# ESC2.net
KiCad netlist of a schematic drawn in Altium Designer
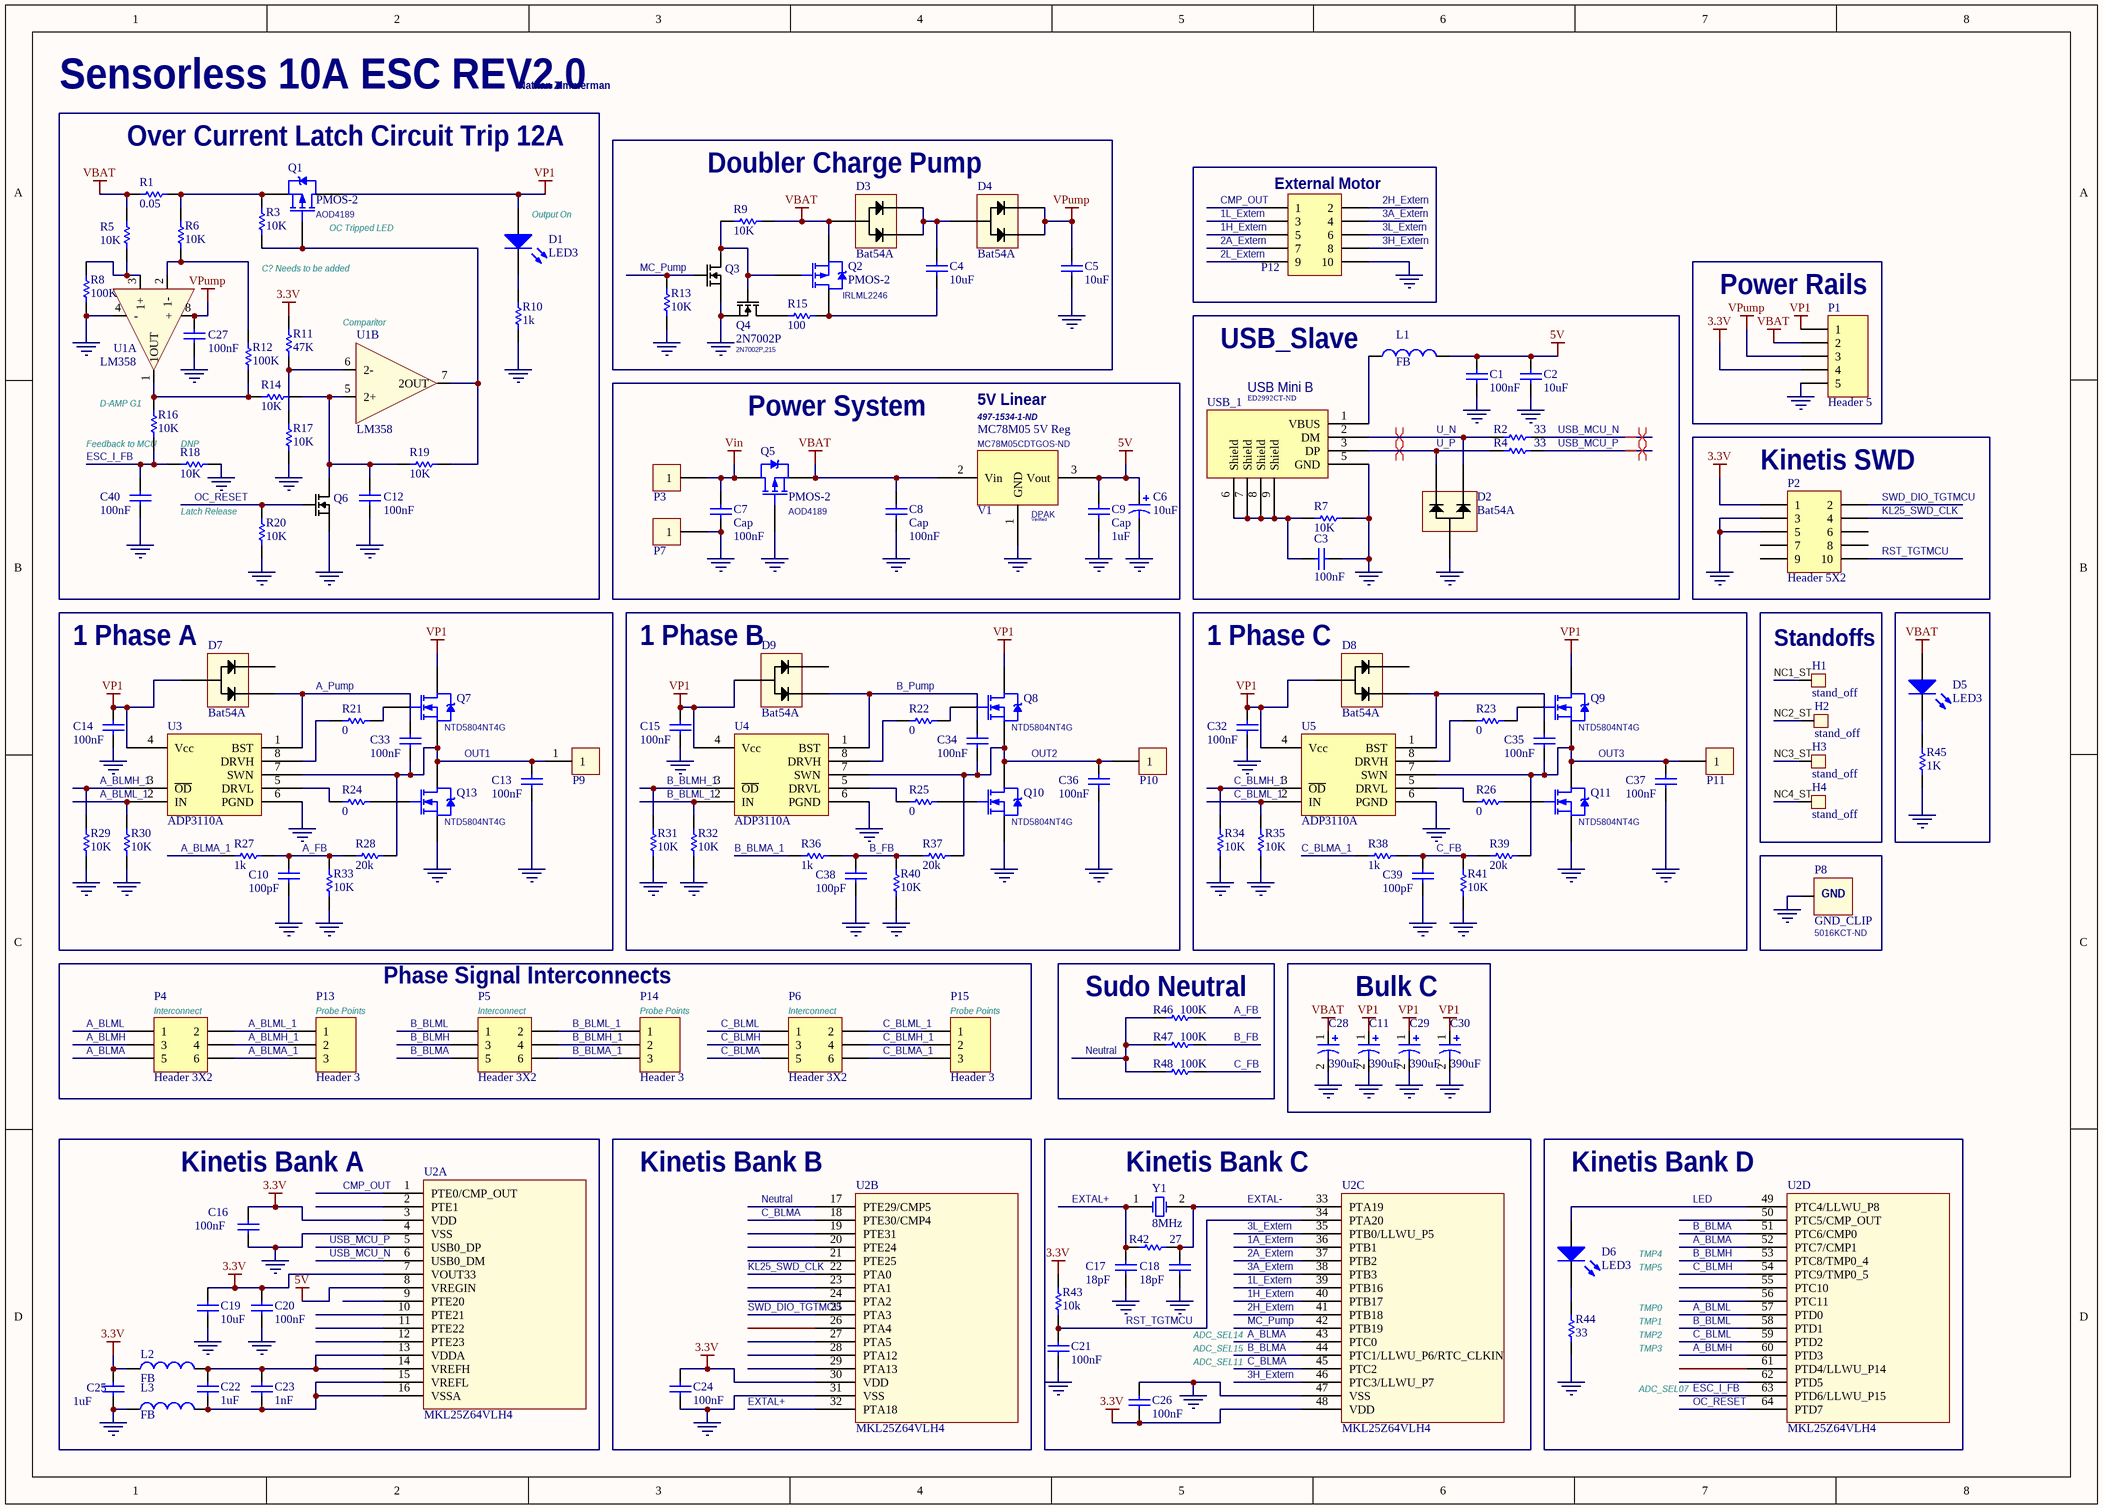
[diagram p0: ESC2.SchDoc]

(export (version "E")
  (design (tool "Eeschema 10.0.6"))
  (components
    (comp (ref "C1")
      (value "100nF")
      (footprint "1608[0603]")
      (description "Capacitor (Semiconductor SIM Model)")
      (fields (field (name "Comment") "0805") (field (name "PUBLISHER") "Altium Limited"))
      (libsource (lib "Miscellaneous Devices") (part "Cap Semi"))
    )
    (comp (ref "C2")
      (value "10uF")
      (footprint "C0805")
      (description "Capacitor (Semiconductor SIM Model)")
      (fields (field (name "Comment") "0805") (field (name "PUBLISHER") "Altium Limited"))
      (libsource (lib "Miscellaneous Devices") (part "Cap Semi"))
    )
    (comp (ref "C3")
      (value "100nF")
      (footprint "1608[0603]")
      (description "Capacitor (Semiconductor SIM Model)")
      (fields (field (name "Comment") "0805") (field (name "PUBLISHER") "Altium Limited"))
      (libsource (lib "Miscellaneous Devices") (part "Cap Semi"))
    )
    (comp (ref "C4")
      (value "10uF")
      (footprint "C0805")
      (description "Capacitor (Semiconductor SIM Model)")
      (fields (field (name "Comment") "0805") (field (name "PUBLISHER") "Altium Limited"))
      (libsource (lib "Miscellaneous Devices") (part "Cap Semi"))
    )
    (comp (ref "C5")
      (value "10uF")
      (footprint "C0805")
      (description "Capacitor (Semiconductor SIM Model)")
      (fields (field (name "Comment") "0805") (field (name "PUBLISHER") "Altium Limited"))
      (libsource (lib "Miscellaneous Devices") (part "Cap Semi"))
    )
    (comp (ref "C6")
      (value "10uF")
      (footprint "1206_C")
      (description "Polarized Capacitor (Radial)")
      (fields (field (name "Comment") "Cap Pol1"))
      (libsource (lib "") (part "Cap Pol1_1"))
    )
    (comp (ref "C7")
      (value "Cap")
      (footprint "C0805")
      (description "Capacitor")
      (fields (field (name "ALTIUM_VALUE") "100nF") (field (name "PUBLISHER") "Altium Limited"))
      (libsource (lib "Miscellaneous Devices") (part "Cap"))
    )
    (comp (ref "C8")
      (value "Cap")
      (footprint "C0805")
      (description "Capacitor")
      (fields (field (name "ALTIUM_VALUE") "100nF") (field (name "PUBLISHER") "Altium Limited"))
      (libsource (lib "Miscellaneous Devices") (part "Cap"))
    )
    (comp (ref "C9")
      (value "Cap")
      (footprint "C0805")
      (description "Capacitor")
      (fields (field (name "ALTIUM_VALUE") "1uF") (field (name "PUBLISHER") "Altium Limited"))
      (libsource (lib "Miscellaneous Devices") (part "Cap"))
    )
    (comp (ref "C10")
      (value "100pF")
      (footprint "1608[0603]")
      (description "Capacitor (Semiconductor SIM Model)")
      (fields (field (name "Comment") "0805") (field (name "PUBLISHER") "Altium Limited"))
      (libsource (lib "Miscellaneous Devices") (part "Cap Semi"))
    )
    (comp (ref "C11")
      (value "390uF")
      (footprint "EEE-FPV391UAP")
      (description "Polarized Capacitor (Radial)")
      (fields (field (name "PART #") "EEE-FPV391UAP") (field (name "Comment") "Cap Pol1"))
      (libsource (lib "Miscellaneous Devices") (part "Cap Pol1"))
    )
    (comp (ref "C12")
      (value "100nF")
      (footprint "1608[0603]")
      (description "Capacitor (Semiconductor SIM Model)")
      (fields (field (name "Comment") "0805"))
      (libsource (lib "Miscellaneous Devices") (part "Cap Semi"))
    )
    (comp (ref "C13")
      (value "100nF")
      (footprint "1608[0603]")
      (description "Capacitor (Semiconductor SIM Model)")
      (fields (field (name "Comment") "0805") (field (name "PUBLISHER") "Altium Limited"))
      (libsource (lib "Miscellaneous Devices") (part "Cap Semi"))
    )
    (comp (ref "C14")
      (value "100nF")
      (footprint "1608[0603]")
      (description "Capacitor (Semiconductor SIM Model)")
      (fields (field (name "Comment") "0805") (field (name "PUBLISHER") "Altium Limited"))
      (libsource (lib "Miscellaneous Devices") (part "Cap Semi"))
    )
    (comp (ref "C15")
      (value "100nF")
      (footprint "1608[0603]")
      (description "Capacitor (Semiconductor SIM Model)")
      (fields (field (name "Comment") "0805") (field (name "PUBLISHER") "Altium Limited"))
      (libsource (lib "Miscellaneous Devices") (part "Cap Semi"))
    )
    (comp (ref "C16")
      (value "100nF")
      (footprint "1608[0603]")
      (description "Capacitor (Semiconductor SIM Model)")
      (fields (field (name "Comment") "0805") (field (name "PUBLISHER") "Altium Limited"))
      (libsource (lib "Miscellaneous Devices") (part "Cap Semi"))
    )
    (comp (ref "C17")
      (value "18pF")
      (footprint "1608[0603]")
      (description "Capacitor (Semiconductor SIM Model)")
      (fields (field (name "Comment") "0805") (field (name "PUBLISHER") "Altium Limited"))
      (libsource (lib "Miscellaneous Devices") (part "Cap Semi"))
    )
    (comp (ref "C18")
      (value "18pF")
      (footprint "1608[0603]")
      (description "Capacitor (Semiconductor SIM Model)")
      (fields (field (name "Comment") "0805") (field (name "PUBLISHER") "Altium Limited"))
      (libsource (lib "Miscellaneous Devices") (part "Cap Semi"))
    )
    (comp (ref "C19")
      (value "10uF")
      (footprint "C0805")
      (description "Capacitor (Semiconductor SIM Model)")
      (fields (field (name "Comment") "0805") (field (name "PUBLISHER") "Altium Limited"))
      (libsource (lib "Miscellaneous Devices") (part "Cap Semi"))
    )
    (comp (ref "C20")
      (value "100nF")
      (footprint "1608[0603]")
      (description "Capacitor (Semiconductor SIM Model)")
      (fields (field (name "Comment") "0805") (field (name "PUBLISHER") "Altium Limited"))
      (libsource (lib "Miscellaneous Devices") (part "Cap Semi"))
    )
    (comp (ref "C21")
      (value "100nF")
      (footprint "1608[0603]")
      (description "Capacitor (Semiconductor SIM Model)")
      (fields (field (name "Comment") "0805") (field (name "PUBLISHER") "Altium Limited"))
      (libsource (lib "Miscellaneous Devices") (part "Cap Semi"))
    )
    (comp (ref "C22")
      (value "1uF")
      (footprint "1608[0603]")
      (description "Capacitor (Semiconductor SIM Model)")
      (fields (field (name "Comment") "0805") (field (name "PUBLISHER") "Altium Limited"))
      (libsource (lib "Miscellaneous Devices") (part "Cap Semi"))
    )
    (comp (ref "C23")
      (value "1nF")
      (footprint "1608[0603]")
      (description "Capacitor (Semiconductor SIM Model)")
      (fields (field (name "Comment") "0805") (field (name "PUBLISHER") "Altium Limited"))
      (libsource (lib "Miscellaneous Devices") (part "Cap Semi"))
    )
    (comp (ref "C24")
      (value "100nF")
      (footprint "1608[0603]")
      (description "Capacitor (Semiconductor SIM Model)")
      (fields (field (name "Comment") "0805") (field (name "PUBLISHER") "Altium Limited"))
      (libsource (lib "Miscellaneous Devices") (part "Cap Semi"))
    )
    (comp (ref "C25")
      (value "1uF")
      (footprint "1608[0603]")
      (description "Capacitor (Semiconductor SIM Model)")
      (fields (field (name "Comment") "0805") (field (name "PUBLISHER") "Altium Limited"))
      (libsource (lib "Miscellaneous Devices") (part "Cap Semi"))
    )
    (comp (ref "C26")
      (value "100nF")
      (footprint "1608[0603]")
      (description "Capacitor (Semiconductor SIM Model)")
      (fields (field (name "Comment") "0805") (field (name "PUBLISHER") "Altium Limited"))
      (libsource (lib "Miscellaneous Devices") (part "Cap Semi"))
    )
    (comp (ref "C27")
      (value "100nF")
      (footprint "1608[0603]")
      (description "Capacitor (Semiconductor SIM Model)")
      (fields (field (name "Comment") "0805"))
      (libsource (lib "Miscellaneous Devices") (part "Cap Semi"))
    )
    (comp (ref "C28")
      (value "390uF")
      (footprint "EEE-FPV391UAP")
      (description "Polarized Capacitor (Radial)")
      (fields (field (name "PART #") "EEE-FPV391UAP") (field (name "Comment") "Cap Pol1"))
      (libsource (lib "Miscellaneous Devices") (part "Cap Pol1"))
    )
    (comp (ref "C29")
      (value "390uF")
      (footprint "EEE-FPV391UAP")
      (description "Polarized Capacitor (Radial)")
      (fields (field (name "PART #") "EEE-FPV391UAP") (field (name "Comment") "Cap Pol1"))
      (libsource (lib "Miscellaneous Devices") (part "Cap Pol1"))
    )
    (comp (ref "C30")
      (value "390uF")
      (footprint "EEE-FPV391UAP")
      (description "Polarized Capacitor (Radial)")
      (fields (field (name "PART #") "EEE-FPV391UAP") (field (name "Comment") "Cap Pol1"))
      (libsource (lib "Miscellaneous Devices") (part "Cap Pol1"))
    )
    (comp (ref "C32")
      (value "100nF")
      (footprint "1608[0603]")
      (description "Capacitor (Semiconductor SIM Model)")
      (fields (field (name "Comment") "0805") (field (name "PUBLISHER") "Altium Limited"))
      (libsource (lib "Miscellaneous Devices") (part "Cap Semi"))
    )
    (comp (ref "C33")
      (value "100nF")
      (footprint "1608[0603]")
      (description "Capacitor (Semiconductor SIM Model)")
      (fields (field (name "Comment") "0805") (field (name "PUBLISHER") "Altium Limited"))
      (libsource (lib "Miscellaneous Devices") (part "Cap Semi"))
    )
    (comp (ref "C34")
      (value "100nF")
      (footprint "1608[0603]")
      (description "Capacitor (Semiconductor SIM Model)")
      (fields (field (name "Comment") "0805") (field (name "PUBLISHER") "Altium Limited"))
      (libsource (lib "Miscellaneous Devices") (part "Cap Semi"))
    )
    (comp (ref "C35")
      (value "100nF")
      (footprint "1608[0603]")
      (description "Capacitor (Semiconductor SIM Model)")
      (fields (field (name "Comment") "0805") (field (name "PUBLISHER") "Altium Limited"))
      (libsource (lib "Miscellaneous Devices") (part "Cap Semi"))
    )
    (comp (ref "C36")
      (value "100nF")
      (footprint "1608[0603]")
      (description "Capacitor (Semiconductor SIM Model)")
      (fields (field (name "Comment") "0805") (field (name "PUBLISHER") "Altium Limited"))
      (libsource (lib "Miscellaneous Devices") (part "Cap Semi"))
    )
    (comp (ref "C37")
      (value "100nF")
      (footprint "1608[0603]")
      (description "Capacitor (Semiconductor SIM Model)")
      (fields (field (name "Comment") "0805") (field (name "PUBLISHER") "Altium Limited"))
      (libsource (lib "Miscellaneous Devices") (part "Cap Semi"))
    )
    (comp (ref "C38")
      (value "100pF")
      (footprint "1608[0603]")
      (description "Capacitor (Semiconductor SIM Model)")
      (fields (field (name "Comment") "0805") (field (name "PUBLISHER") "Altium Limited"))
      (libsource (lib "Miscellaneous Devices") (part "Cap Semi"))
    )
    (comp (ref "C39")
      (value "100pF")
      (footprint "1608[0603]")
      (description "Capacitor (Semiconductor SIM Model)")
      (fields (field (name "Comment") "0805") (field (name "PUBLISHER") "Altium Limited"))
      (libsource (lib "Miscellaneous Devices") (part "Cap Semi"))
    )
    (comp (ref "C40")
      (value "100nF")
      (footprint "1608[0603]")
      (description "Capacitor (Semiconductor SIM Model)")
      (fields (field (name "Comment") "0805") (field (name "PUBLISHER") "Altium Limited"))
      (libsource (lib "Miscellaneous Devices") (part "Cap Semi"))
    )
    (comp (ref "D1")
      (value "LED3")
      (footprint "6-0805_L")
      (description "Typical BLUE SiC LED")
      (fields (field (name "PUBLISHER") "Altium Limited"))
      (libsource (lib "Miscellaneous Devices") (part "LED3"))
    )
    (comp (ref "D2")
      (value "Bat54A")
      (footprint "SOT-23B_N")
      (description "Bat45C")
      (libsource (lib "GSOT05CGS08") (part "Bat45C"))
    )
    (comp (ref "D3")
      (value "Bat54A")
      (footprint "SOT-23B_N")
      (description "Bat45C")
      (libsource (lib "GSOT05CGS08") (part "Bat45C"))
    )
    (comp (ref "D4")
      (value "Bat54A")
      (footprint "SOT-23B_N")
      (description "Bat45C")
      (libsource (lib "GSOT05CGS08") (part "Bat45C"))
    )
    (comp (ref "D5")
      (value "LED3")
      (footprint "6-0805_L")
      (description "Typical BLUE SiC LED")
      (fields (field (name "PUBLISHER") "Altium Limited"))
      (libsource (lib "Miscellaneous Devices") (part "LED3"))
    )
    (comp (ref "D6")
      (value "LED3")
      (footprint "6-0805_L")
      (description "Typical BLUE SiC LED")
      (fields (field (name "PUBLISHER") "Altium Limited"))
      (libsource (lib "Miscellaneous Devices") (part "LED3"))
    )
    (comp (ref "D7")
      (value "Bat54A")
      (footprint "SOT-23B_N")
      (description "Bat45C")
      (libsource (lib "GSOT05CGS08") (part "Bat45C"))
    )
    (comp (ref "D8")
      (value "Bat54A")
      (footprint "SOT-23B_N")
      (description "Bat45C")
      (libsource (lib "GSOT05CGS08") (part "Bat45C"))
    )
    (comp (ref "D9")
      (value "Bat54A")
      (footprint "SOT-23B_N")
      (description "Bat45C")
      (libsource (lib "GSOT05CGS08") (part "Bat45C"))
    )
    (comp (ref "H1")
      (value "stand_off")
      (footprint "4-40_screw_hole")
      (libsource (lib "pcb_standoff") (part "stand_off"))
    )
    (comp (ref "H2")
      (value "stand_off")
      (footprint "4-40_screw_hole")
      (libsource (lib "pcb_standoff") (part "stand_off"))
    )
    (comp (ref "H3")
      (value "stand_off")
      (footprint "4-40_screw_hole")
      (libsource (lib "pcb_standoff") (part "stand_off"))
    )
    (comp (ref "H4")
      (value "stand_off")
      (footprint "4-40_screw_hole")
      (libsource (lib "pcb_standoff") (part "stand_off"))
    )
    (comp (ref "L1")
      (value "FB")
      (footprint "1608[0603]")
      (description "Inductor")
      (libsource (lib "Miscellaneous Devices") (part "Inductor"))
    )
    (comp (ref "L2")
      (value "FB")
      (footprint "1608[0603]")
      (description "Inductor")
      (libsource (lib "Miscellaneous Devices") (part "Inductor"))
    )
    (comp (ref "L3")
      (value "FB")
      (footprint "1608[0603]")
      (description "Inductor")
      (libsource (lib "Miscellaneous Devices") (part "Inductor"))
    )
    (comp (ref "P1")
      (value "Header 5")
      (footprint "HDR1X5")
      (description "Header, 5-Pin")
      (fields (field (name "PUBLISHER") "Altium Limited"))
      (libsource (lib "Miscellaneous Connectors") (part "Header 5"))
    )
    (comp (ref "P2")
      (value "Header 5X2")
      (footprint "MHDR2X5")
      (description "Header, 5-Pin, Dual row")
      (fields (field (name "PUBLISHER") "Altium Limited"))
      (libsource (lib "Miscellaneous Connectors") (part "Header 5X2"))
    )
    (comp (ref "P3") (value "Header") (footprint "8191_K") (libsource (lib "Header1") (part "Header1h1")))
    (comp (ref "P4")
      (value "Header 3X2")
      (footprint "HDR2X3")
      (description "Header, 3-Pin, Dual row")
      (fields (field (name "PUBLISHER") "Altium Limited"))
      (libsource (lib "Miscellaneous Connectors") (part "Header 3X2"))
    )
    (comp (ref "P5")
      (value "Header 3X2")
      (footprint "HDR2X3")
      (description "Header, 3-Pin, Dual row")
      (fields (field (name "PUBLISHER") "Altium Limited"))
      (libsource (lib "Miscellaneous Connectors") (part "Header 3X2"))
    )
    (comp (ref "P6")
      (value "Header 3X2")
      (footprint "HDR2X3")
      (description "Header, 3-Pin, Dual row")
      (fields (field (name "PUBLISHER") "Altium Limited"))
      (libsource (lib "Miscellaneous Connectors") (part "Header 3X2"))
    )
    (comp (ref "P7") (value "Header") (footprint "8191_K") (libsource (lib "Header1") (part "Header1h1")))
    (comp (ref "P8")
      (value "GND_CLIP")
      (footprint "GND_CLIP")
      (fields (field (name "ALTIUM_UNNAMED_1") "5016KCT-ND"))
      (libsource (lib "GND_CLIP") (part "GND_CLIP"))
    )
    (comp (ref "P9") (value "Header") (footprint "8191_K") (libsource (lib "") (part "Header1h1_1")))
    (comp (ref "P10") (value "Header") (footprint "8191_K") (libsource (lib "Header1") (part "Header1h1")))
    (comp (ref "P11") (value "Header") (footprint "8191_K") (libsource (lib "Header1") (part "Header1h1")))
    (comp (ref "P12")
      (value "Header 5X2")
      (footprint "HDR2X5")
      (description "Header, 5-Pin, Dual row")
      (fields (field (name "PUBLISHER") "Altium Limited"))
      (libsource (lib "Miscellaneous Connectors") (part "Header 5X2"))
    )
    (comp (ref "P13")
      (value "Header 3")
      (footprint "HDR1X3")
      (description "Header, 3-Pin")
      (fields (field (name "PUBLISHER") "Altium Limited"))
      (libsource (lib "Miscellaneous Connectors") (part "Header 3"))
    )
    (comp (ref "P14")
      (value "Header 3")
      (footprint "HDR1X3")
      (description "Header, 3-Pin")
      (fields (field (name "PUBLISHER") "Altium Limited"))
      (libsource (lib "Miscellaneous Connectors") (part "Header 3"))
    )
    (comp (ref "P15")
      (value "Header 3")
      (footprint "HDR1X3")
      (description "Header, 3-Pin")
      (fields (field (name "PUBLISHER") "Altium Limited"))
      (libsource (lib "Miscellaneous Connectors") (part "Header 3"))
    )
    (comp (ref "Q1")
      (value "PMOS-2")
      (footprint "TO228P970-3_4AM")
      (description "P-Channel Power MOSFET")
      (fields (field (name "ALTIUM_UNNAMED_1") "AOD4189"))
      (libsource (lib "Miscellaneous Devices") (part "PMOS-2"))
    )
    (comp (ref "Q2")
      (value "PMOS-2")
      (footprint "SOT-23_M")
      (description "P-Channel Power MOSFET")
      (fields (field (name "ALTIUM_UNNAMED_1") "IRLML2246"))
      (libsource (lib "") (part "PMOS-2_1"))
    )
    (comp (ref "Q3") (value "2N7002P") (footprint "SOT-23_M") (libsource (lib "2N7002P215") (part "2N7002P")))
    (comp (ref "Q4")
      (value "2N7002P")
      (footprint "SOT-23_M")
      (fields (field (name "ALTIUM_UNNAMED_1") "2N7002P,215"))
      (libsource (lib "2N7002P215") (part "2N7002P"))
    )
    (comp (ref "Q5")
      (value "PMOS-2")
      (footprint "TO228P970-3_4AM")
      (description "P-Channel Power MOSFET")
      (fields (field (name "ALTIUM_UNNAMED_1") "AOD4189"))
      (libsource (lib "Miscellaneous Devices") (part "PMOS-2"))
    )
    (comp (ref "Q6") (value "2N7002P") (footprint "SOT-23_M") (libsource (lib "2N7002P215") (part "2N7002P")))
    (comp (ref "Q7")
      (value "NMOS-2")
      (footprint "TO228P970-3_4AM")
      (description "N-Channel Power MOSFET")
      (fields (field (name "ALTIUM_UNNAMED_1") "NTD5804NT4G"))
      (libsource (lib "Miscellaneous Devices") (part "NMOS-2"))
    )
    (comp (ref "Q8")
      (value "NMOS-2")
      (footprint "TO228P970-3_4AM")
      (description "N-Channel Power MOSFET")
      (fields (field (name "ALTIUM_UNNAMED_1") "NTD5804NT4G"))
      (libsource (lib "Miscellaneous Devices") (part "NMOS-2"))
    )
    (comp (ref "Q9")
      (value "NMOS-2")
      (footprint "TO228P970-3_4AM")
      (description "N-Channel Power MOSFET")
      (fields (field (name "ALTIUM_UNNAMED_1") "NTD5804NT4G"))
      (libsource (lib "Miscellaneous Devices") (part "NMOS-2"))
    )
    (comp (ref "Q10")
      (value "NMOS-2")
      (footprint "TO228P970-3_4AM")
      (description "N-Channel Power MOSFET")
      (fields (field (name "ALTIUM_UNNAMED_1") "NTD5804NT4G"))
      (libsource (lib "Miscellaneous Devices") (part "NMOS-2"))
    )
    (comp (ref "Q11")
      (value "NMOS-2")
      (footprint "TO228P970-3_4AM")
      (description "N-Channel Power MOSFET")
      (fields (field (name "ALTIUM_UNNAMED_1") "NTD5804NT4G"))
      (libsource (lib "Miscellaneous Devices") (part "NMOS-2"))
    )
    (comp (ref "Q13")
      (value "NMOS-2")
      (footprint "TO228P970-3_4AM")
      (description "N-Channel Power MOSFET")
      (fields (field (name "ALTIUM_UNNAMED_1") "NTD5804NT4G"))
      (libsource (lib "Miscellaneous Devices") (part "NMOS-2"))
    )
    (comp (ref "R1")
      (value "0.05")
      (footprint "RESC6432AM")
      (description "Resistor")
      (fields (field (name "Comment") "Res1") (field (name "PUBLISHER") "Altium Limited"))
      (libsource (lib "Miscellaneous Devices") (part "Res1"))
    )
    (comp (ref "R2")
      (value "33")
      (footprint "1608[0603]")
      (description "Resistor")
      (fields (field (name "Comment") "Res1") (field (name "PUBLISHER") "Altium Limited"))
      (libsource (lib "Miscellaneous Devices") (part "Res1"))
    )
    (comp (ref "R3")
      (value "10K")
      (footprint "1608[0603]")
      (description "Resistor")
      (fields (field (name "Comment") "Res1") (field (name "PUBLISHER") "Altium Limited"))
      (libsource (lib "Miscellaneous Devices") (part "Res1"))
    )
    (comp (ref "R4")
      (value "33")
      (footprint "1608[0603]")
      (description "Resistor")
      (fields (field (name "Comment") "Res1") (field (name "PUBLISHER") "Altium Limited"))
      (libsource (lib "Miscellaneous Devices") (part "Res1"))
    )
    (comp (ref "R5")
      (value "10K")
      (footprint "1608[0603]")
      (description "Resistor")
      (fields (field (name "Comment") "Res1") (field (name "PUBLISHER") "Altium Limited"))
      (libsource (lib "Miscellaneous Devices") (part "Res1"))
    )
    (comp (ref "R6")
      (value "10K")
      (footprint "1608[0603]")
      (description "Resistor")
      (fields (field (name "Comment") "Res1") (field (name "PUBLISHER") "Altium Limited"))
      (libsource (lib "Miscellaneous Devices") (part "Res1"))
    )
    (comp (ref "R7")
      (value "10K")
      (footprint "1608[0603]")
      (description "Resistor")
      (fields (field (name "Comment") "Res1") (field (name "PUBLISHER") "Altium Limited"))
      (libsource (lib "Miscellaneous Devices") (part "Res1"))
    )
    (comp (ref "R8")
      (value "100K")
      (footprint "1608[0603]")
      (description "Resistor")
      (fields (field (name "Comment") "Res1") (field (name "PUBLISHER") "Altium Limited"))
      (libsource (lib "Miscellaneous Devices") (part "Res1"))
    )
    (comp (ref "R9")
      (value "10K")
      (footprint "1608[0603]")
      (description "Resistor")
      (fields (field (name "Comment") "Res1") (field (name "PUBLISHER") "Altium Limited"))
      (libsource (lib "Miscellaneous Devices") (part "Res1"))
    )
    (comp (ref "R10")
      (value "1k")
      (footprint "1608[0603]")
      (description "Resistor")
      (fields (field (name "Comment") "Res1") (field (name "PUBLISHER") "Altium Limited"))
      (libsource (lib "Miscellaneous Devices") (part "Res1"))
    )
    (comp (ref "R11")
      (value "47K")
      (footprint "1608[0603]")
      (description "Resistor")
      (fields (field (name "Comment") "Res1") (field (name "PUBLISHER") "Altium Limited"))
      (libsource (lib "Miscellaneous Devices") (part "Res1"))
    )
    (comp (ref "R12")
      (value "100K")
      (footprint "1608[0603]")
      (description "Resistor")
      (fields (field (name "Comment") "Res1") (field (name "PUBLISHER") "Altium Limited"))
      (libsource (lib "Miscellaneous Devices") (part "Res1"))
    )
    (comp (ref "R13")
      (value "10K")
      (footprint "1608[0603]")
      (description "Resistor")
      (fields (field (name "Comment") "Res1") (field (name "PUBLISHER") "Altium Limited"))
      (libsource (lib "Miscellaneous Devices") (part "Res1"))
    )
    (comp (ref "R14")
      (value "10K")
      (footprint "1608[0603]")
      (description "Resistor")
      (fields (field (name "Comment") "Res1") (field (name "PUBLISHER") "Altium Limited"))
      (libsource (lib "Miscellaneous Devices") (part "Res1"))
    )
    (comp (ref "R15")
      (value "100")
      (footprint "1608[0603]")
      (description "Resistor")
      (fields (field (name "Comment") "Res1") (field (name "PUBLISHER") "Altium Limited"))
      (libsource (lib "Miscellaneous Devices") (part "Res1"))
    )
    (comp (ref "R16")
      (value "10K")
      (footprint "1608[0603]")
      (description "Resistor")
      (fields (field (name "Comment") "Res1") (field (name "PUBLISHER") "Altium Limited"))
      (libsource (lib "Miscellaneous Devices") (part "Res1"))
    )
    (comp (ref "R17")
      (value "10K")
      (footprint "1608[0603]")
      (description "Resistor")
      (fields (field (name "Comment") "Res1") (field (name "PUBLISHER") "Altium Limited"))
      (libsource (lib "Miscellaneous Devices") (part "Res1"))
    )
    (comp (ref "R18")
      (value "10K")
      (footprint "1608[0603]")
      (description "Resistor")
      (fields (field (name "Comment") "Res1") (field (name "PUBLISHER") "Altium Limited"))
      (libsource (lib "Miscellaneous Devices") (part "Res1"))
    )
    (comp (ref "R19")
      (value "10K")
      (footprint "1608[0603]")
      (description "Resistor")
      (fields (field (name "Comment") "Res1") (field (name "PUBLISHER") "Altium Limited"))
      (libsource (lib "Miscellaneous Devices") (part "Res1"))
    )
    (comp (ref "R20")
      (value "10K")
      (footprint "1608[0603]")
      (description "Resistor")
      (fields (field (name "Comment") "Res1") (field (name "PUBLISHER") "Altium Limited"))
      (libsource (lib "Miscellaneous Devices") (part "Res1"))
    )
    (comp (ref "R21")
      (value "0")
      (footprint "1608[0603]")
      (description "Resistor")
      (fields (field (name "Comment") "Res1") (field (name "PUBLISHER") "Altium Limited"))
      (libsource (lib "Miscellaneous Devices") (part "Res1"))
    )
    (comp (ref "R22")
      (value "0")
      (footprint "1608[0603]")
      (description "Resistor")
      (fields (field (name "Comment") "Res1") (field (name "PUBLISHER") "Altium Limited"))
      (libsource (lib "Miscellaneous Devices") (part "Res1"))
    )
    (comp (ref "R23")
      (value "0")
      (footprint "1608[0603]")
      (description "Resistor")
      (fields (field (name "Comment") "Res1") (field (name "PUBLISHER") "Altium Limited"))
      (libsource (lib "Miscellaneous Devices") (part "Res1"))
    )
    (comp (ref "R24")
      (value "0")
      (footprint "1608[0603]")
      (description "Resistor")
      (fields (field (name "Comment") "Res1") (field (name "PUBLISHER") "Altium Limited"))
      (libsource (lib "Miscellaneous Devices") (part "Res1"))
    )
    (comp (ref "R25")
      (value "0")
      (footprint "1608[0603]")
      (description "Resistor")
      (fields (field (name "Comment") "Res1") (field (name "PUBLISHER") "Altium Limited"))
      (libsource (lib "Miscellaneous Devices") (part "Res1"))
    )
    (comp (ref "R26")
      (value "0")
      (footprint "1608[0603]")
      (description "Resistor")
      (fields (field (name "Comment") "Res1") (field (name "PUBLISHER") "Altium Limited"))
      (libsource (lib "Miscellaneous Devices") (part "Res1"))
    )
    (comp (ref "R27")
      (value "1k")
      (footprint "1608[0603]")
      (description "Resistor")
      (fields (field (name "Comment") "Res1") (field (name "PUBLISHER") "Altium Limited"))
      (libsource (lib "Miscellaneous Devices") (part "Res1"))
    )
    (comp (ref "R28")
      (value "20k")
      (footprint "1608[0603]")
      (description "Resistor")
      (fields (field (name "Comment") "Res1") (field (name "PUBLISHER") "Altium Limited"))
      (libsource (lib "Miscellaneous Devices") (part "Res1"))
    )
    (comp (ref "R29")
      (value "10K")
      (footprint "1608[0603]")
      (description "Resistor")
      (fields (field (name "Comment") "Res1") (field (name "PUBLISHER") "Altium Limited"))
      (libsource (lib "Miscellaneous Devices") (part "Res1"))
    )
    (comp (ref "R30")
      (value "10K")
      (footprint "1608[0603]")
      (description "Resistor")
      (fields (field (name "Comment") "Res1") (field (name "PUBLISHER") "Altium Limited"))
      (libsource (lib "Miscellaneous Devices") (part "Res1"))
    )
    (comp (ref "R31")
      (value "10K")
      (footprint "1608[0603]")
      (description "Resistor")
      (fields (field (name "Comment") "Res1") (field (name "PUBLISHER") "Altium Limited"))
      (libsource (lib "Miscellaneous Devices") (part "Res1"))
    )
    (comp (ref "R32")
      (value "10K")
      (footprint "1608[0603]")
      (description "Resistor")
      (fields (field (name "Comment") "Res1") (field (name "PUBLISHER") "Altium Limited"))
      (libsource (lib "Miscellaneous Devices") (part "Res1"))
    )
    (comp (ref "R33")
      (value "10K")
      (footprint "1608[0603]")
      (description "Resistor")
      (fields (field (name "Comment") "Res1") (field (name "PUBLISHER") "Altium Limited"))
      (libsource (lib "Miscellaneous Devices") (part "Res1"))
    )
    (comp (ref "R34")
      (value "10K")
      (footprint "1608[0603]")
      (description "Resistor")
      (fields (field (name "Comment") "Res1") (field (name "PUBLISHER") "Altium Limited"))
      (libsource (lib "Miscellaneous Devices") (part "Res1"))
    )
    (comp (ref "R35")
      (value "10K")
      (footprint "1608[0603]")
      (description "Resistor")
      (fields (field (name "Comment") "Res1") (field (name "PUBLISHER") "Altium Limited"))
      (libsource (lib "Miscellaneous Devices") (part "Res1"))
    )
    (comp (ref "R36")
      (value "1k")
      (footprint "1608[0603]")
      (description "Resistor")
      (fields (field (name "Comment") "Res1") (field (name "PUBLISHER") "Altium Limited"))
      (libsource (lib "Miscellaneous Devices") (part "Res1"))
    )
    (comp (ref "R37")
      (value "20k")
      (footprint "1608[0603]")
      (description "Resistor")
      (fields (field (name "Comment") "Res1") (field (name "PUBLISHER") "Altium Limited"))
      (libsource (lib "Miscellaneous Devices") (part "Res1"))
    )
    (comp (ref "R38")
      (value "1k")
      (footprint "1608[0603]")
      (description "Resistor")
      (fields (field (name "Comment") "Res1") (field (name "PUBLISHER") "Altium Limited"))
      (libsource (lib "Miscellaneous Devices") (part "Res1"))
    )
    (comp (ref "R39")
      (value "20k")
      (footprint "1608[0603]")
      (description "Resistor")
      (fields (field (name "Comment") "Res1") (field (name "PUBLISHER") "Altium Limited"))
      (libsource (lib "Miscellaneous Devices") (part "Res1"))
    )
    (comp (ref "R40")
      (value "10K")
      (footprint "1608[0603]")
      (description "Resistor")
      (fields (field (name "Comment") "Res1") (field (name "PUBLISHER") "Altium Limited"))
      (libsource (lib "Miscellaneous Devices") (part "Res1"))
    )
    (comp (ref "R41")
      (value "10K")
      (footprint "1608[0603]")
      (description "Resistor")
      (fields (field (name "Comment") "Res1") (field (name "PUBLISHER") "Altium Limited"))
      (libsource (lib "Miscellaneous Devices") (part "Res1"))
    )
    (comp (ref "R42")
      (value "27")
      (footprint "1608[0603]")
      (description "Resistor")
      (fields (field (name "Comment") "Res1") (field (name "PUBLISHER") "Altium Limited"))
      (libsource (lib "Miscellaneous Devices") (part "Res1"))
    )
    (comp (ref "R43")
      (value "10k")
      (footprint "1608[0603]")
      (description "Resistor")
      (fields (field (name "Comment") "Res1") (field (name "PUBLISHER") "Altium Limited"))
      (libsource (lib "Miscellaneous Devices") (part "Res1"))
    )
    (comp (ref "R44")
      (value "33")
      (footprint "1608[0603]")
      (description "Resistor")
      (fields (field (name "Comment") "Res1") (field (name "PUBLISHER") "Altium Limited"))
      (libsource (lib "Miscellaneous Devices") (part "Res1"))
    )
    (comp (ref "R45")
      (value "1K")
      (footprint "1608[0603]")
      (description "Resistor")
      (fields (field (name "Comment") "Res1") (field (name "PUBLISHER") "Altium Limited"))
      (libsource (lib "Miscellaneous Devices") (part "Res1"))
    )
    (comp (ref "R46")
      (value "100K")
      (footprint "1608[0603]")
      (description "Resistor")
      (fields (field (name "Comment") "Res1") (field (name "PUBLISHER") "Altium Limited"))
      (libsource (lib "Miscellaneous Devices") (part "Res1"))
    )
    (comp (ref "R47")
      (value "100K")
      (footprint "1608[0603]")
      (description "Resistor")
      (fields (field (name "Comment") "Res1") (field (name "PUBLISHER") "Altium Limited"))
      (libsource (lib "Miscellaneous Devices") (part "Res1"))
    )
    (comp (ref "R48")
      (value "100K")
      (footprint "1608[0603]")
      (description "Resistor")
      (fields (field (name "Comment") "Res1") (field (name "PUBLISHER") "Altium Limited"))
      (libsource (lib "Miscellaneous Devices") (part "Res1"))
    )
    (comp (ref "U1")
      (value "LM358")
      (footprint "SOIC127P600-8BM")
      (description "LM358 Op Amp")
      (libsource (lib "LM358_New") (part "LM358"))
    )
    (comp (ref "U2")
      (value "MKL25Z64VLH4")
      (footprint "TSQFP50P1200X1200-64M")
      (description "MKL25Z64VLH4 MCU")
      (libsource (lib "MKL25Z64VLH4") (part "MKL25Z64VLH4"))
    )
    (comp (ref "U3")
      (value "ADP3110A")
      (footprint "SOIC127P600-8BM")
      (libsource (lib "ADP3110A") (part "ADP3110A"))
    )
    (comp (ref "U4")
      (value "ADP3110A")
      (footprint "SOIC127P600-8BM")
      (libsource (lib "ADP3110A") (part "ADP3110A"))
    )
    (comp (ref "U5")
      (value "ADP3110A")
      (footprint "SOIC127P600-8BM")
      (libsource (lib "ADP3110A") (part "ADP3110A"))
    )
    (comp (ref "USB_1")
      (value "USB-M2xFxx")
      (footprint "USB-M2xFxx")
      (description "USB Mini-B for USB-M2xFxx")
      (fields (field (name "DIGIKEY") "ED2992CT-ND"))
      (libsource (lib "USB-M2xFxx") (part "USB-M2xFxx"))
    )
    (comp (ref "V1")
      (value "MC78M05 5V Reg")
      (footprint "TO228P970-3_4AM")
      (description "MCP1702 5V REG")
      (fields (field (name "ALTIUM_UNNAMED_1") "497-1534-1-ND"))
      (libsource (lib "MCP1702") (part "MCP1702"))
    )
    (comp (ref "Y1")
      (value "8MHz")
      (footprint "crystal")
      (description "Crystal Oscillator")
      (libsource (lib "Miscellaneous Devices") (part "XTAL"))
    )
  )
  (nets
    (net (code "1") (name "/1A_Extern") (class "Default")
      (node (ref "U2") (pin "36") (pinfunction "PTB1_36") (pintype "passive"))
    )
    (net (code "2") (name "/1H_Extern") (class "Default")
      (node (ref "P12") (pin "5") (pinfunction "5_5") (pintype "passive"))
      (node (ref "U2") (pin "40") (pinfunction "PTB17_40") (pintype "passive"))
    )
    (net (code "3") (name "/1L_Extern") (class "Default")
      (node (ref "P12") (pin "3") (pinfunction "3_3") (pintype "passive"))
      (node (ref "U2") (pin "39") (pinfunction "PTB16_39") (pintype "passive"))
    )
    (net (code "4") (name "/2A_Extern") (class "Default")
      (node (ref "P12") (pin "7") (pinfunction "7_7") (pintype "passive"))
      (node (ref "U2") (pin "37") (pinfunction "PTB2_37") (pintype "passive"))
    )
    (net (code "5") (name "/2H_Extern") (class "Default")
      (node (ref "P12") (pin "2") (pinfunction "2_2") (pintype "passive"))
      (node (ref "U2") (pin "41") (pinfunction "PTB18_41") (pintype "passive"))
    )
    (net (code "6") (name "/2L_Extern") (class "Default")
      (node (ref "P12") (pin "9") (pinfunction "9_9") (pintype "passive"))
    )
    (net (code "7") (name "/3A_Extern") (class "Default")
      (node (ref "P12") (pin "4") (pinfunction "4_4") (pintype "passive"))
      (node (ref "U2") (pin "38") (pinfunction "PTB3_38") (pintype "passive"))
    )
    (net (code "8") (name "/3H_Extern") (class "Default")
      (node (ref "P12") (pin "8") (pinfunction "8_8") (pintype "passive"))
      (node (ref "U2") (pin "46") (pinfunction "PTC3/LLWU_P7_46") (pintype "passive"))
    )
    (net (code "9") (name "/3L_Extern") (class "Default")
      (node (ref "P12") (pin "6") (pinfunction "6_6") (pintype "passive"))
      (node (ref "U2") (pin "35") (pinfunction "PTB0/LLWU_P5_35") (pintype "passive"))
    )
    (net (code "10") (name "/A_BLMA") (class "Default")
      (node (ref "P4") (pin "5") (pinfunction "5_5") (pintype "passive"))
      (node (ref "U2") (pin "43") (pinfunction "PTC0_43") (pintype "passive"))
      (node (ref "U2") (pin "52") (pinfunction "PTC7/CMP1_52") (pintype "passive"))
    )
    (net (code "11") (name "/A_BLMA_1") (class "Default")
      (node (ref "P13") (pin "3") (pinfunction "3_3") (pintype "passive"))
      (node (ref "P4") (pin "6") (pinfunction "6_6") (pintype "passive"))
      (node (ref "R27") (pin "2") (pinfunction "2_2") (pintype "passive"))
    )
    (net (code "12") (name "/A_BLMH") (class "Default")
      (node (ref "P4") (pin "3") (pinfunction "3_3") (pintype "passive"))
      (node (ref "U2") (pin "60") (pinfunction "PTD3_60") (pintype "passive"))
    )
    (net (code "13") (name "/A_BLMH_1") (class "Default")
      (node (ref "P13") (pin "2") (pinfunction "2_2") (pintype "passive"))
      (node (ref "P4") (pin "4") (pinfunction "4_4") (pintype "passive"))
      (node (ref "R29") (pin "1") (pinfunction "1_1") (pintype "passive"))
      (node (ref "U3") (pin "3") (pinfunction "~{OD}_3") (pintype "passive"))
    )
    (net (code "14") (name "/A_BLML") (class "Default")
      (node (ref "P4") (pin "1") (pinfunction "1_1") (pintype "passive"))
      (node (ref "U2") (pin "57") (pinfunction "PTD0_57") (pintype "passive"))
    )
    (net (code "15") (name "/A_BLML_1") (class "Default")
      (node (ref "P13") (pin "1") (pinfunction "1_1") (pintype "passive"))
      (node (ref "P4") (pin "2") (pinfunction "2_2") (pintype "passive"))
      (node (ref "R30") (pin "1") (pinfunction "1_1") (pintype "passive"))
      (node (ref "U3") (pin "2") (pinfunction "IN_2") (pintype "passive"))
    )
    (net (code "16") (name "/A_FB") (class "Default")
      (node (ref "C10") (pin "2") (pinfunction "2_2") (pintype "passive"))
      (node (ref "R27") (pin "1") (pinfunction "1_1") (pintype "passive"))
      (node (ref "R28") (pin "2") (pinfunction "2_2") (pintype "passive"))
      (node (ref "R33") (pin "1") (pinfunction "1_1") (pintype "passive"))
      (node (ref "R46") (pin "2") (pinfunction "2_2") (pintype "passive"))
    )
    (net (code "17") (name "/A_Pump") (class "Default")
      (node (ref "C33") (pin "2") (pinfunction "2_2") (pintype "passive"))
      (node (ref "D7") (pin "1") (pinfunction "0_1") (pintype "passive"))
      (node (ref "U3") (pin "1") (pinfunction "BST_1") (pintype "passive"))
    )
    (net (code "18") (name "/B_BLMA") (class "Default")
      (node (ref "P5") (pin "5") (pinfunction "5_5") (pintype "passive"))
      (node (ref "U2") (pin "44") (pinfunction "PTC1/LLWU_P6/RTC_CLKIN_44") (pintype "passive"))
      (node (ref "U2") (pin "51") (pinfunction "PTC6/CMP0_51") (pintype "passive"))
    )
    (net (code "19") (name "/B_BLMA_1") (class "Default")
      (node (ref "P14") (pin "3") (pinfunction "3_3") (pintype "passive"))
      (node (ref "P5") (pin "6") (pinfunction "6_6") (pintype "passive"))
      (node (ref "R36") (pin "2") (pinfunction "2_2") (pintype "passive"))
    )
    (net (code "20") (name "/B_BLMH") (class "Default")
      (node (ref "P5") (pin "3") (pinfunction "3_3") (pintype "passive"))
      (node (ref "U2") (pin "53") (pinfunction "PTC8/TMP0_4_53") (pintype "passive"))
    )
    (net (code "21") (name "/B_BLMH_1") (class "Default")
      (node (ref "P14") (pin "2") (pinfunction "2_2") (pintype "passive"))
      (node (ref "P5") (pin "4") (pinfunction "4_4") (pintype "passive"))
      (node (ref "R31") (pin "1") (pinfunction "1_1") (pintype "passive"))
      (node (ref "U4") (pin "3") (pinfunction "~{OD}_3") (pintype "passive"))
    )
    (net (code "22") (name "/B_BLML") (class "Default")
      (node (ref "P5") (pin "1") (pinfunction "1_1") (pintype "passive"))
      (node (ref "U2") (pin "58") (pinfunction "PTD1_58") (pintype "passive"))
    )
    (net (code "23") (name "/B_BLML_1") (class "Default")
      (node (ref "P14") (pin "1") (pinfunction "1_1") (pintype "passive"))
      (node (ref "P5") (pin "2") (pinfunction "2_2") (pintype "passive"))
      (node (ref "R32") (pin "1") (pinfunction "1_1") (pintype "passive"))
      (node (ref "U4") (pin "2") (pinfunction "IN_2") (pintype "passive"))
    )
    (net (code "24") (name "/B_FB") (class "Default")
      (node (ref "C38") (pin "2") (pinfunction "2_2") (pintype "passive"))
      (node (ref "R36") (pin "1") (pinfunction "1_1") (pintype "passive"))
      (node (ref "R37") (pin "2") (pinfunction "2_2") (pintype "passive"))
      (node (ref "R40") (pin "1") (pinfunction "1_1") (pintype "passive"))
      (node (ref "R47") (pin "2") (pinfunction "2_2") (pintype "passive"))
    )
    (net (code "25") (name "/B_Pump") (class "Default")
      (node (ref "C34") (pin "2") (pinfunction "2_2") (pintype "passive"))
      (node (ref "D9") (pin "1") (pinfunction "0_1") (pintype "passive"))
      (node (ref "U4") (pin "1") (pinfunction "BST_1") (pintype "passive"))
    )
    (net (code "26") (name "/CMP_OUT") (class "Default")
      (node (ref "P12") (pin "1") (pinfunction "1_1") (pintype "passive"))
      (node (ref "U2") (pin "1") (pinfunction "PTE0_1") (pintype "passive"))
    )
    (net (code "27") (name "/C_BLMA") (class "Default")
      (node (ref "P6") (pin "5") (pinfunction "5_5") (pintype "passive"))
      (node (ref "U2") (pin "18") (pinfunction "PTE30_18") (pintype "passive"))
      (node (ref "U2") (pin "45") (pinfunction "PTC2_45") (pintype "passive"))
    )
    (net (code "28") (name "/C_BLMA_1") (class "Default")
      (node (ref "P15") (pin "3") (pinfunction "3_3") (pintype "passive"))
      (node (ref "P6") (pin "6") (pinfunction "6_6") (pintype "passive"))
      (node (ref "R38") (pin "2") (pinfunction "2_2") (pintype "passive"))
    )
    (net (code "29") (name "/C_BLMH") (class "Default")
      (node (ref "P6") (pin "3") (pinfunction "3_3") (pintype "passive"))
      (node (ref "U2") (pin "54") (pinfunction "PTC9/TMP0_5_54") (pintype "passive"))
    )
    (net (code "30") (name "/C_BLMH_1") (class "Default")
      (node (ref "P15") (pin "2") (pinfunction "2_2") (pintype "passive"))
      (node (ref "P6") (pin "4") (pinfunction "4_4") (pintype "passive"))
      (node (ref "R34") (pin "1") (pinfunction "1_1") (pintype "passive"))
      (node (ref "U5") (pin "3") (pinfunction "~{OD}_3") (pintype "passive"))
    )
    (net (code "31") (name "/C_BLML") (class "Default")
      (node (ref "P6") (pin "1") (pinfunction "1_1") (pintype "passive"))
      (node (ref "U2") (pin "59") (pinfunction "PTD2_59") (pintype "passive"))
    )
    (net (code "32") (name "/C_BLML_1") (class "Default")
      (node (ref "P15") (pin "1") (pinfunction "1_1") (pintype "passive"))
      (node (ref "P6") (pin "2") (pinfunction "2_2") (pintype "passive"))
      (node (ref "R35") (pin "1") (pinfunction "1_1") (pintype "passive"))
      (node (ref "U5") (pin "2") (pinfunction "IN_2") (pintype "passive"))
    )
    (net (code "33") (name "/C_FB") (class "Default")
      (node (ref "C39") (pin "2") (pinfunction "2_2") (pintype "passive"))
      (node (ref "R38") (pin "1") (pinfunction "1_1") (pintype "passive"))
      (node (ref "R39") (pin "2") (pinfunction "2_2") (pintype "passive"))
      (node (ref "R41") (pin "1") (pinfunction "1_1") (pintype "passive"))
      (node (ref "R48") (pin "2") (pinfunction "2_2") (pintype "passive"))
    )
    (net (code "34") (name "/ESC_I_FB") (class "Default")
      (node (ref "C40") (pin "2") (pinfunction "2_2") (pintype "passive"))
      (node (ref "R16") (pin "1") (pinfunction "1_1") (pintype "passive"))
      (node (ref "R18") (pin "2") (pinfunction "2_2") (pintype "passive"))
      (node (ref "U2") (pin "63") (pinfunction "PTD6/LLWU_P15_63") (pintype "passive"))
    )
    (net (code "35") (name "/EXTAL+") (class "Default")
      (node (ref "C17") (pin "2") (pinfunction "2_2") (pintype "passive"))
      (node (ref "R42") (pin "1") (pinfunction "1_1") (pintype "passive"))
      (node (ref "U2") (pin "32") (pinfunction "PTA18_32") (pintype "passive"))
      (node (ref "Y1") (pin "1") (pinfunction "OSC1_1") (pintype "passive"))
    )
    (net (code "36") (name "/EXTAL-") (class "Default")
      (node (ref "C18") (pin "2") (pinfunction "2_2") (pintype "passive"))
      (node (ref "R42") (pin "2") (pinfunction "2_2") (pintype "passive"))
      (node (ref "U2") (pin "33") (pinfunction "PTA19_33") (pintype "passive"))
      (node (ref "Y1") (pin "2") (pinfunction "OSC2_2") (pintype "passive"))
    )
    (net (code "37") (name "/KL25_SWD_CLK") (class "Default")
      (node (ref "P2") (pin "4") (pinfunction "4_4") (pintype "passive"))
      (node (ref "U2") (pin "22") (pinfunction "PTA0_22") (pintype "passive"))
    )
    (net (code "38") (name "/LED") (class "Default")
      (node (ref "D6") (pin "1") (pinfunction "A_1") (pintype "passive"))
      (node (ref "U2") (pin "49") (pinfunction "PTC4/LLWU_P8_49") (pintype "passive"))
    )
    (net (code "39") (name "/MC_Pump") (class "Default")
      (node (ref "Q3") (pin "1") (pinfunction "G_1") (pintype "passive"))
      (node (ref "R13") (pin "1") (pinfunction "1_1") (pintype "passive"))
      (node (ref "U2") (pin "42") (pinfunction "PTB19_42") (pintype "passive"))
    )
    (net (code "40") (name "/NC1_ST") (class "Default")
      (node (ref "H1") (pin "1") (pinfunction "0_1") (pintype "passive"))
    )
    (net (code "41") (name "/NC2_ST") (class "Default")
      (node (ref "H2") (pin "1") (pinfunction "0_1") (pintype "passive"))
    )
    (net (code "42") (name "/NC3_ST") (class "Default")
      (node (ref "H3") (pin "1") (pinfunction "0_1") (pintype "passive"))
    )
    (net (code "43") (name "/NC4_ST") (class "Default")
      (node (ref "H4") (pin "1") (pinfunction "0_1") (pintype "passive"))
    )
    (net (code "44") (name "/Neutral") (class "Default")
      (node (ref "R46") (pin "1") (pinfunction "1_1") (pintype "passive"))
      (node (ref "R47") (pin "1") (pinfunction "1_1") (pintype "passive"))
      (node (ref "R48") (pin "1") (pinfunction "1_1") (pintype "passive"))
      (node (ref "U2") (pin "17") (pinfunction "PTE29_17") (pintype "passive"))
    )
    (net (code "45") (name "/OC_RESET") (class "Default")
      (node (ref "Q6") (pin "1") (pinfunction "G_1") (pintype "passive"))
      (node (ref "R20") (pin "1") (pinfunction "1_1") (pintype "passive"))
      (node (ref "U2") (pin "64") (pinfunction "PTD7_64") (pintype "passive"))
    )
    (net (code "46") (name "/OUT1") (class "Default")
      (node (ref "C13") (pin "2") (pinfunction "2_2") (pintype "passive"))
      (node (ref "C33") (pin "1") (pinfunction "1_1") (pintype "passive"))
      (node (ref "P9") (pin "1") (pinfunction "1_1") (pintype "passive"))
      (node (ref "Q13") (pin "4") (pinfunction "D_4") (pintype "passive"))
      (node (ref "Q7") (pin "3") (pinfunction "S_3") (pintype "passive"))
      (node (ref "R28") (pin "1") (pinfunction "1_1") (pintype "passive"))
      (node (ref "U3") (pin "7") (pinfunction "SWN_7") (pintype "passive"))
    )
    (net (code "47") (name "/OUT2") (class "Default")
      (node (ref "C34") (pin "1") (pinfunction "1_1") (pintype "passive"))
      (node (ref "C36") (pin "2") (pinfunction "2_2") (pintype "passive"))
      (node (ref "P10") (pin "1") (pinfunction "1_1") (pintype "passive"))
      (node (ref "Q10") (pin "4") (pinfunction "D_4") (pintype "passive"))
      (node (ref "Q8") (pin "3") (pinfunction "S_3") (pintype "passive"))
      (node (ref "R37") (pin "1") (pinfunction "1_1") (pintype "passive"))
      (node (ref "U4") (pin "7") (pinfunction "SWN_7") (pintype "passive"))
    )
    (net (code "48") (name "/OUT3") (class "Default")
      (node (ref "C35") (pin "1") (pinfunction "1_1") (pintype "passive"))
      (node (ref "C37") (pin "2") (pinfunction "2_2") (pintype "passive"))
      (node (ref "P11") (pin "1") (pinfunction "1_1") (pintype "passive"))
      (node (ref "Q11") (pin "4") (pinfunction "D_4") (pintype "passive"))
      (node (ref "Q9") (pin "3") (pinfunction "S_3") (pintype "passive"))
      (node (ref "R39") (pin "1") (pinfunction "1_1") (pintype "passive"))
      (node (ref "U5") (pin "7") (pinfunction "SWN_7") (pintype "passive"))
    )
    (net (code "49") (name "/RST_TGTMCU") (class "Default")
      (node (ref "C21") (pin "2") (pinfunction "2_2") (pintype "passive"))
      (node (ref "P2") (pin "10") (pinfunction "10_10") (pintype "passive"))
      (node (ref "R43") (pin "1") (pinfunction "1_1") (pintype "passive"))
      (node (ref "U2") (pin "34") (pinfunction "PTA20_34") (pintype "passive"))
    )
    (net (code "50") (name "/SWD_DIO_TGTMCU") (class "Default")
      (node (ref "P2") (pin "2") (pinfunction "2_2") (pintype "passive"))
      (node (ref "U2") (pin "25") (pinfunction "PTA3_25") (pintype "passive"))
    )
    (net (code "51") (name "/USB_MCU_N") (class "Default")
      (node (ref "R2") (pin "2") (pinfunction "2_2") (pintype "passive"))
      (node (ref "U2") (pin "6") (pinfunction "USB0_DM_6") (pintype "passive"))
    )
    (net (code "52") (name "/USB_MCU_P") (class "Default")
      (node (ref "R4") (pin "2") (pinfunction "2_2") (pintype "passive"))
      (node (ref "U2") (pin "5") (pinfunction "USB0_DP_5") (pintype "passive"))
    )
    (net (code "53") (name "/U_N") (class "Default")
      (node (ref "D2") (pin "1") (pinfunction "0_1") (pintype "passive"))
      (node (ref "R2") (pin "1") (pinfunction "1_1") (pintype "passive"))
      (node (ref "USB_1") (pin "2") (pinfunction "DM_2") (pintype "passive"))
    )
    (net (code "54") (name "/U_P") (class "Default")
      (node (ref "D2") (pin "2") (pinfunction "0_2") (pintype "passive"))
      (node (ref "R4") (pin "1") (pinfunction "1_1") (pintype "passive"))
      (node (ref "USB_1") (pin "3") (pinfunction "DP_3") (pintype "passive"))
    )
    (net (code "55") (name "3.3V") (class "Default")
      (node (ref "C16") (pin "2") (pinfunction "2_2") (pintype "passive"))
      (node (ref "C19") (pin "1") (pinfunction "1_1") (pintype "passive"))
      (node (ref "C20") (pin "1") (pinfunction "1_1") (pintype "passive"))
      (node (ref "C24") (pin "2") (pinfunction "2_2") (pintype "passive"))
      (node (ref "C25") (pin "2") (pinfunction "2_2") (pintype "passive"))
      (node (ref "C26") (pin "1") (pinfunction "1_1") (pintype "passive"))
      (node (ref "L2") (pin "2") (pinfunction "2_2") (pintype "passive"))
      (node (ref "P1") (pin "4") (pinfunction "4_4") (pintype "passive"))
      (node (ref "P2") (pin "1") (pinfunction "1_1") (pintype "passive"))
      (node (ref "R11") (pin "1") (pinfunction "1_1") (pintype "passive"))
      (node (ref "R43") (pin "2") (pinfunction "2_2") (pintype "passive"))
      (node (ref "U2") (pin "3") (pinfunction "VDD_3") (pintype "passive"))
      (node (ref "U2") (pin "30") (pinfunction "VDD_30") (pintype "passive"))
      (node (ref "U2") (pin "48") (pinfunction "VDD_48") (pintype "passive"))
      (node (ref "U2") (pin "7") (pinfunction "VOUT33_7") (pintype "passive"))
    )
    (net (code "56") (name "5V") (class "Default")
      (node (ref "C1") (pin "1") (pinfunction "1_1") (pintype "passive"))
      (node (ref "C2") (pin "1") (pinfunction "1_1") (pintype "passive"))
      (node (ref "C6") (pin "1") (pinfunction "1_1") (pintype "passive"))
      (node (ref "C9") (pin "2") (pinfunction "2_2") (pintype "passive"))
      (node (ref "L1") (pin "1") (pinfunction "1_1") (pintype "passive"))
      (node (ref "U2") (pin "8") (pinfunction "VREGIN_8") (pintype "passive"))
      (node (ref "V1") (pin "3") (pinfunction "Vout_3") (pintype "passive"))
    )
    (net (code "57") (name "GND") (class "Default")
      (node (ref "C1") (pin "2") (pinfunction "2_2") (pintype "passive"))
      (node (ref "C10") (pin "1") (pinfunction "1_1") (pintype "passive"))
      (node (ref "C11") (pin "2") (pinfunction "2_2") (pintype "passive"))
      (node (ref "C12") (pin "1") (pinfunction "1_1") (pintype "passive"))
      (node (ref "C13") (pin "1") (pinfunction "1_1") (pintype "passive"))
      (node (ref "C14") (pin "1") (pinfunction "1_1") (pintype "passive"))
      (node (ref "C15") (pin "1") (pinfunction "1_1") (pintype "passive"))
      (node (ref "C16") (pin "1") (pinfunction "1_1") (pintype "passive"))
      (node (ref "C17") (pin "1") (pinfunction "1_1") (pintype "passive"))
      (node (ref "C18") (pin "1") (pinfunction "1_1") (pintype "passive"))
      (node (ref "C19") (pin "2") (pinfunction "2_2") (pintype "passive"))
      (node (ref "C2") (pin "2") (pinfunction "2_2") (pintype "passive"))
      (node (ref "C20") (pin "2") (pinfunction "2_2") (pintype "passive"))
      (node (ref "C21") (pin "1") (pinfunction "1_1") (pintype "passive"))
      (node (ref "C24") (pin "1") (pinfunction "1_1") (pintype "passive"))
      (node (ref "C25") (pin "1") (pinfunction "1_1") (pintype "passive"))
      (node (ref "C26") (pin "2") (pinfunction "2_2") (pintype "passive"))
      (node (ref "C27") (pin "1") (pinfunction "1_1") (pintype "passive"))
      (node (ref "C28") (pin "2") (pinfunction "2_2") (pintype "passive"))
      (node (ref "C29") (pin "2") (pinfunction "2_2") (pintype "passive"))
      (node (ref "C3") (pin "2") (pinfunction "2_2") (pintype "passive"))
      (node (ref "C30") (pin "2") (pinfunction "2_2") (pintype "passive"))
      (node (ref "C32") (pin "1") (pinfunction "1_1") (pintype "passive"))
      (node (ref "C36") (pin "1") (pinfunction "1_1") (pintype "passive"))
      (node (ref "C37") (pin "1") (pinfunction "1_1") (pintype "passive"))
      (node (ref "C38") (pin "1") (pinfunction "1_1") (pintype "passive"))
      (node (ref "C39") (pin "1") (pinfunction "1_1") (pintype "passive"))
      (node (ref "C40") (pin "1") (pinfunction "1_1") (pintype "passive"))
      (node (ref "C5") (pin "2") (pinfunction "2_2") (pintype "passive"))
      (node (ref "C6") (pin "2") (pinfunction "2_2") (pintype "passive"))
      (node (ref "C7") (pin "1") (pinfunction "1_1") (pintype "passive"))
      (node (ref "C8") (pin "1") (pinfunction "1_1") (pintype "passive"))
      (node (ref "C9") (pin "1") (pinfunction "1_1") (pintype "passive"))
      (node (ref "D2") (pin "3") (pinfunction "0_3") (pintype "passive"))
      (node (ref "L3") (pin "2") (pinfunction "2_2") (pintype "passive"))
      (node (ref "P1") (pin "5") (pinfunction "5_5") (pintype "passive"))
      (node (ref "P12") (pin "10") (pinfunction "10_10") (pintype "passive"))
      (node (ref "P2") (pin "3") (pinfunction "3_3") (pintype "passive"))
      (node (ref "P2") (pin "5") (pinfunction "5_5") (pintype "passive"))
      (node (ref "P7") (pin "1") (pinfunction "1_1") (pintype "passive"))
      (node (ref "P8") (pin "1") (pinfunction "GND_1") (pintype "passive"))
      (node (ref "Q10") (pin "3") (pinfunction "S_3") (pintype "passive"))
      (node (ref "Q11") (pin "3") (pinfunction "S_3") (pintype "passive"))
      (node (ref "Q13") (pin "3") (pinfunction "S_3") (pintype "passive"))
      (node (ref "Q3") (pin "2") (pinfunction "S_2") (pintype "passive"))
      (node (ref "Q4") (pin "2") (pinfunction "S_2") (pintype "passive"))
      (node (ref "Q5") (pin "1") (pinfunction "G_1") (pintype "passive"))
      (node (ref "Q6") (pin "2") (pinfunction "S_2") (pintype "passive"))
      (node (ref "R10") (pin "2") (pinfunction "2_2") (pintype "passive"))
      (node (ref "R13") (pin "2") (pinfunction "2_2") (pintype "passive"))
      (node (ref "R17") (pin "2") (pinfunction "2_2") (pintype "passive"))
      (node (ref "R18") (pin "1") (pinfunction "1_1") (pintype "passive"))
      (node (ref "R20") (pin "2") (pinfunction "2_2") (pintype "passive"))
      (node (ref "R29") (pin "2") (pinfunction "2_2") (pintype "passive"))
      (node (ref "R30") (pin "2") (pinfunction "2_2") (pintype "passive"))
      (node (ref "R31") (pin "2") (pinfunction "2_2") (pintype "passive"))
      (node (ref "R32") (pin "2") (pinfunction "2_2") (pintype "passive"))
      (node (ref "R33") (pin "2") (pinfunction "2_2") (pintype "passive"))
      (node (ref "R34") (pin "2") (pinfunction "2_2") (pintype "passive"))
      (node (ref "R35") (pin "2") (pinfunction "2_2") (pintype "passive"))
      (node (ref "R40") (pin "2") (pinfunction "2_2") (pintype "passive"))
      (node (ref "R41") (pin "2") (pinfunction "2_2") (pintype "passive"))
      (node (ref "R44") (pin "2") (pinfunction "2_2") (pintype "passive"))
      (node (ref "R45") (pin "2") (pinfunction "2_2") (pintype "passive"))
      (node (ref "R7") (pin "1") (pinfunction "1_1") (pintype "passive"))
      (node (ref "R8") (pin "1") (pinfunction "1_1") (pintype "passive"))
      (node (ref "U1") (pin "4") (pinfunction "-_4") (pintype "passive"))
      (node (ref "U2") (pin "31") (pinfunction "VSS_31") (pintype "passive"))
      (node (ref "U2") (pin "4") (pinfunction "VSS_4") (pintype "passive"))
      (node (ref "U2") (pin "47") (pinfunction "VSS_47") (pintype "passive"))
      (node (ref "U3") (pin "6") (pinfunction "PGND_6") (pintype "passive"))
      (node (ref "U4") (pin "6") (pinfunction "PGND_6") (pintype "passive"))
      (node (ref "U5") (pin "6") (pinfunction "PGND_6") (pintype "passive"))
      (node (ref "USB_1") (pin "5") (pinfunction "GND_5") (pintype "passive"))
      (node (ref "V1") (pin "1") (pinfunction "GND_1") (pintype "passive"))
    )
    (net (code "58") (name "Net-(C3-Pad1)") (class "Default")
      (node (ref "C3") (pin "1") (pinfunction "1_1") (pintype "passive"))
      (node (ref "R7") (pin "2") (pinfunction "2_2") (pintype "passive"))
      (node (ref "USB_1") (pin "6") (pinfunction "Shield_6") (pintype "passive"))
      (node (ref "USB_1") (pin "7") (pinfunction "Shield_7") (pintype "passive"))
      (node (ref "USB_1") (pin "8") (pinfunction "Shield_8") (pintype "passive"))
      (node (ref "USB_1") (pin "9") (pinfunction "Shield_9") (pintype "passive"))
    )
    (net (code "59") (name "Net-(C4-Pad1)") (class "Default")
      (node (ref "C4") (pin "1") (pinfunction "1_1") (pintype "passive"))
      (node (ref "D3") (pin "1") (pinfunction "0_1") (pintype "passive"))
      (node (ref "D3") (pin "2") (pinfunction "0_2") (pintype "passive"))
      (node (ref "D4") (pin "3") (pinfunction "0_3") (pintype "passive"))
    )
    (net (code "60") (name "Net-(D1-K)") (class "Default")
      (node (ref "D1") (pin "2") (pinfunction "K_2") (pintype "passive"))
      (node (ref "R10") (pin "1") (pinfunction "1_1") (pintype "passive"))
    )
    (net (code "61") (name "Net-(D5-K)") (class "Default")
      (node (ref "D5") (pin "2") (pinfunction "K_2") (pintype "passive"))
      (node (ref "R45") (pin "1") (pinfunction "1_1") (pintype "passive"))
    )
    (net (code "62") (name "Net-(D6-K)") (class "Default")
      (node (ref "D6") (pin "2") (pinfunction "K_2") (pintype "passive"))
      (node (ref "R44") (pin "1") (pinfunction "1_1") (pintype "passive"))
    )
    (net (code "63") (name "Net-(Q1-G)") (class "Default")
      (node (ref "Q1") (pin "1") (pinfunction "G_1") (pintype "passive"))
      (node (ref "R19") (pin "2") (pinfunction "2_2") (pintype "passive"))
      (node (ref "R3") (pin "2") (pinfunction "2_2") (pintype "passive"))
      (node (ref "U1") (pin "7") (pinfunction "2OUT_7") (pintype "passive"))
    )
    (net (code "64") (name "Net-(Q1-S)") (class "Default")
      (node (ref "Q1") (pin "3") (pinfunction "S_3") (pintype "passive"))
      (node (ref "R1") (pin "2") (pinfunction "2_2") (pintype "passive"))
      (node (ref "R3") (pin "1") (pinfunction "1_1") (pintype "passive"))
      (node (ref "R6") (pin "2") (pinfunction "2_2") (pintype "passive"))
    )
    (net (code "65") (name "Net-(Q2-D)") (class "Default")
      (node (ref "C4") (pin "2") (pinfunction "2_2") (pintype "passive"))
      (node (ref "Q2") (pin "3") (pinfunction "D_3") (pintype "passive"))
      (node (ref "R15") (pin "1") (pinfunction "1_1") (pintype "passive"))
    )
    (net (code "66") (name "Net-(Q2-G)") (class "Default")
      (node (ref "Q2") (pin "1") (pinfunction "G_1") (pintype "passive"))
      (node (ref "Q3") (pin "3") (pinfunction "D_3") (pintype "passive"))
      (node (ref "Q4") (pin "1") (pinfunction "G_1") (pintype "passive"))
      (node (ref "R9") (pin "2") (pinfunction "2_2") (pintype "passive"))
    )
    (net (code "67") (name "Net-(Q4-D)") (class "Default")
      (node (ref "Q4") (pin "3") (pinfunction "D_3") (pintype "passive"))
      (node (ref "R15") (pin "2") (pinfunction "2_2") (pintype "passive"))
    )
    (net (code "68") (name "Net-(Q6-D)") (class "Default")
      (node (ref "C12") (pin "2") (pinfunction "2_2") (pintype "passive"))
      (node (ref "Q6") (pin "3") (pinfunction "D_3") (pintype "passive"))
      (node (ref "R14") (pin "2") (pinfunction "2_2") (pintype "passive"))
      (node (ref "R19") (pin "1") (pinfunction "1_1") (pintype "passive"))
      (node (ref "U1") (pin "5") (pinfunction "2+_5") (pintype "passive"))
    )
    (net (code "69") (name "Net-(Q7-G)") (class "Default")
      (node (ref "Q7") (pin "1") (pinfunction "G_1") (pintype "passive"))
      (node (ref "R21") (pin "1") (pinfunction "1_1") (pintype "passive"))
    )
    (net (code "70") (name "Net-(Q8-G)") (class "Default")
      (node (ref "Q8") (pin "1") (pinfunction "G_1") (pintype "passive"))
      (node (ref "R22") (pin "1") (pinfunction "1_1") (pintype "passive"))
    )
    (net (code "71") (name "Net-(Q9-G)") (class "Default")
      (node (ref "Q9") (pin "1") (pinfunction "G_1") (pintype "passive"))
      (node (ref "R23") (pin "1") (pinfunction "1_1") (pintype "passive"))
    )
    (net (code "72") (name "Net-(Q10-G)") (class "Default")
      (node (ref "Q10") (pin "1") (pinfunction "G_1") (pintype "passive"))
      (node (ref "R25") (pin "1") (pinfunction "1_1") (pintype "passive"))
    )
    (net (code "73") (name "Net-(Q11-G)") (class "Default")
      (node (ref "Q11") (pin "1") (pinfunction "G_1") (pintype "passive"))
      (node (ref "R26") (pin "1") (pinfunction "1_1") (pintype "passive"))
    )
    (net (code "74") (name "Net-(Q13-G)") (class "Default")
      (node (ref "Q13") (pin "1") (pinfunction "G_1") (pintype "passive"))
      (node (ref "R24") (pin "1") (pinfunction "1_1") (pintype "passive"))
    )
    (net (code "75") (name "Net-(U1A-1+)") (class "Default")
      (node (ref "R5") (pin "2") (pinfunction "2_2") (pintype "passive"))
      (node (ref "R8") (pin "2") (pinfunction "2_2") (pintype "passive"))
      (node (ref "U1") (pin "3") (pinfunction "1+_3") (pintype "passive"))
    )
    (net (code "76") (name "Net-(U1A-1-)") (class "Default")
      (node (ref "R12") (pin "2") (pinfunction "2_2") (pintype "passive"))
      (node (ref "R6") (pin "1") (pinfunction "1_1") (pintype "passive"))
      (node (ref "U1") (pin "2") (pinfunction "1-_2") (pintype "passive"))
    )
    (net (code "77") (name "Net-(U1A-1OUT)") (class "Default")
      (node (ref "R12") (pin "1") (pinfunction "1_1") (pintype "passive"))
      (node (ref "R14") (pin "1") (pinfunction "1_1") (pintype "passive"))
      (node (ref "R16") (pin "2") (pinfunction "2_2") (pintype "passive"))
      (node (ref "U1") (pin "1") (pinfunction "1OUT_1") (pintype "passive"))
    )
    (net (code "78") (name "Net-(U1B-2-)") (class "Default")
      (node (ref "R11") (pin "2") (pinfunction "2_2") (pintype "passive"))
      (node (ref "R17") (pin "1") (pinfunction "1_1") (pintype "passive"))
      (node (ref "U1") (pin "6") (pinfunction "2-_6") (pintype "passive"))
    )
    (net (code "79") (name "Net-(U2A-VDDA)") (class "Default")
      (node (ref "C22") (pin "2") (pinfunction "2_2") (pintype "passive"))
      (node (ref "C23") (pin "2") (pinfunction "2_2") (pintype "passive"))
      (node (ref "L2") (pin "1") (pinfunction "1_1") (pintype "passive"))
      (node (ref "U2") (pin "13") (pinfunction "VDDA_13") (pintype "passive"))
      (node (ref "U2") (pin "14") (pinfunction "VREFH_14") (pintype "passive"))
    )
    (net (code "80") (name "Net-(U2A-VREFL)") (class "Default")
      (node (ref "C22") (pin "1") (pinfunction "1_1") (pintype "passive"))
      (node (ref "C23") (pin "1") (pinfunction "1_1") (pintype "passive"))
      (node (ref "L3") (pin "1") (pinfunction "1_1") (pintype "passive"))
      (node (ref "U2") (pin "15") (pinfunction "VREFL_15") (pintype "passive"))
      (node (ref "U2") (pin "16") (pinfunction "VSSA_16") (pintype "passive"))
    )
    (net (code "81") (name "Net-(U3-DRVH)") (class "Default")
      (node (ref "R21") (pin "2") (pinfunction "2_2") (pintype "passive"))
      (node (ref "U3") (pin "8") (pinfunction "DRVH_8") (pintype "passive"))
    )
    (net (code "82") (name "Net-(U3-DRVL)") (class "Default")
      (node (ref "R24") (pin "2") (pinfunction "2_2") (pintype "passive"))
      (node (ref "U3") (pin "5") (pinfunction "DRVL_5") (pintype "passive"))
    )
    (net (code "83") (name "Net-(U4-DRVH)") (class "Default")
      (node (ref "R22") (pin "2") (pinfunction "2_2") (pintype "passive"))
      (node (ref "U4") (pin "8") (pinfunction "DRVH_8") (pintype "passive"))
    )
    (net (code "84") (name "Net-(U4-DRVL)") (class "Default")
      (node (ref "R25") (pin "2") (pinfunction "2_2") (pintype "passive"))
      (node (ref "U4") (pin "5") (pinfunction "DRVL_5") (pintype "passive"))
    )
    (net (code "85") (name "Net-(U5-BST)") (class "Default")
      (node (ref "C35") (pin "2") (pinfunction "2_2") (pintype "passive"))
      (node (ref "D8") (pin "1") (pinfunction "0_1") (pintype "passive"))
      (node (ref "U5") (pin "1") (pinfunction "BST_1") (pintype "passive"))
    )
    (net (code "86") (name "Net-(U5-DRVH)") (class "Default")
      (node (ref "R23") (pin "2") (pinfunction "2_2") (pintype "passive"))
      (node (ref "U5") (pin "8") (pinfunction "DRVH_8") (pintype "passive"))
    )
    (net (code "87") (name "Net-(U5-DRVL)") (class "Default")
      (node (ref "R26") (pin "2") (pinfunction "2_2") (pintype "passive"))
      (node (ref "U5") (pin "5") (pinfunction "DRVL_5") (pintype "passive"))
    )
    (net (code "88") (name "Net-(USB_1-VBUS)") (class "Default")
      (node (ref "L1") (pin "2") (pinfunction "2_2") (pintype "passive"))
      (node (ref "USB_1") (pin "1") (pinfunction "VBUS_1") (pintype "passive"))
    )
    (net (code "89") (name "VBAT") (class "Default")
      (node (ref "C28") (pin "1") (pinfunction "1_1") (pintype "passive"))
      (node (ref "C8") (pin "2") (pinfunction "2_2") (pintype "passive"))
      (node (ref "D3") (pin "3") (pinfunction "0_3") (pintype "passive"))
      (node (ref "D5") (pin "1") (pinfunction "A_1") (pintype "passive"))
      (node (ref "P1") (pin "2") (pinfunction "2_2") (pintype "passive"))
      (node (ref "Q2") (pin "2") (pinfunction "S_2") (pintype "passive"))
      (node (ref "Q5") (pin "3") (pinfunction "S_3") (pintype "passive"))
      (node (ref "R1") (pin "1") (pinfunction "1_1") (pintype "passive"))
      (node (ref "R5") (pin "1") (pinfunction "1_1") (pintype "passive"))
      (node (ref "R9") (pin "1") (pinfunction "1_1") (pintype "passive"))
      (node (ref "V1") (pin "2") (pinfunction "Vin_2") (pintype "passive"))
    )
    (net (code "90") (name "VP1") (class "Default")
      (node (ref "C11") (pin "1") (pinfunction "1_1") (pintype "passive"))
      (node (ref "C14") (pin "2") (pinfunction "2_2") (pintype "passive"))
      (node (ref "C15") (pin "2") (pinfunction "2_2") (pintype "passive"))
      (node (ref "C29") (pin "1") (pinfunction "1_1") (pintype "passive"))
      (node (ref "C30") (pin "1") (pinfunction "1_1") (pintype "passive"))
      (node (ref "C32") (pin "2") (pinfunction "2_2") (pintype "passive"))
      (node (ref "D1") (pin "1") (pinfunction "A_1") (pintype "passive"))
      (node (ref "D7") (pin "3") (pinfunction "0_3") (pintype "passive"))
      (node (ref "D8") (pin "3") (pinfunction "0_3") (pintype "passive"))
      (node (ref "D9") (pin "3") (pinfunction "0_3") (pintype "passive"))
      (node (ref "P1") (pin "1") (pinfunction "1_1") (pintype "passive"))
      (node (ref "Q1") (pin "4") (pinfunction "D_4") (pintype "passive"))
      (node (ref "Q7") (pin "4") (pinfunction "D_4") (pintype "passive"))
      (node (ref "Q8") (pin "4") (pinfunction "D_4") (pintype "passive"))
      (node (ref "Q9") (pin "4") (pinfunction "D_4") (pintype "passive"))
      (node (ref "U3") (pin "4") (pinfunction "Vcc_4") (pintype "passive"))
      (node (ref "U4") (pin "4") (pinfunction "Vcc_4") (pintype "passive"))
      (node (ref "U5") (pin "4") (pinfunction "Vcc_4") (pintype "passive"))
    )
    (net (code "91") (name "VPump") (class "Default")
      (node (ref "C27") (pin "2") (pinfunction "2_2") (pintype "passive"))
      (node (ref "C5") (pin "1") (pinfunction "1_1") (pintype "passive"))
      (node (ref "D4") (pin "1") (pinfunction "0_1") (pintype "passive"))
      (node (ref "D4") (pin "2") (pinfunction "0_2") (pintype "passive"))
      (node (ref "P1") (pin "3") (pinfunction "3_3") (pintype "passive"))
      (node (ref "U1") (pin "8") (pinfunction "+_8") (pintype "passive"))
    )
    (net (code "92") (name "Vin") (class "Default")
      (node (ref "C7") (pin "2") (pinfunction "2_2") (pintype "passive"))
      (node (ref "P3") (pin "1") (pinfunction "1_1") (pintype "passive"))
      (node (ref "Q5") (pin "4") (pinfunction "D_4") (pintype "passive"))
    )
    (net (code "93") (name "unconnected-(D7-0-Pad2)") (class "Default")
      (node (ref "D7") (pin "2") (pinfunction "0_2") (pintype "passive"))
    )
    (net (code "94") (name "unconnected-(D8-0-Pad2)") (class "Default")
      (node (ref "D8") (pin "2") (pinfunction "0_2") (pintype "passive"))
    )
    (net (code "95") (name "unconnected-(D9-0-Pad2)") (class "Default")
      (node (ref "D9") (pin "2") (pinfunction "0_2") (pintype "passive"))
    )
    (net (code "96") (name "unconnected-(P2-Pad6)") (class "Default")
      (node (ref "P2") (pin "6") (pinfunction "6_6") (pintype "passive"))
    )
    (net (code "97") (name "unconnected-(P2-Pad7)") (class "Default")
      (node (ref "P2") (pin "7") (pinfunction "7_7") (pintype "passive"))
    )
    (net (code "98") (name "unconnected-(P2-Pad8)") (class "Default")
      (node (ref "P2") (pin "8") (pinfunction "8_8") (pintype "passive"))
    )
    (net (code "99") (name "unconnected-(P2-Pad9)") (class "Default")
      (node (ref "P2") (pin "9") (pinfunction "9_9") (pintype "passive"))
    )
    (net (code "100") (name "unconnected-(U2A-PTE1-Pad2)") (class "Default")
      (node (ref "U2") (pin "2") (pinfunction "PTE1_2") (pintype "passive"))
    )
    (net (code "101") (name "unconnected-(U2A-PTE20-Pad9)") (class "Default")
      (node (ref "U2") (pin "9") (pinfunction "PTE20_9") (pintype "passive"))
    )
    (net (code "102") (name "unconnected-(U2A-PTE21-Pad10)") (class "Default")
      (node (ref "U2") (pin "10") (pinfunction "PTE21_10") (pintype "passive"))
    )
    (net (code "103") (name "unconnected-(U2A-PTE22-Pad11)") (class "Default")
      (node (ref "U2") (pin "11") (pinfunction "PTE22_11") (pintype "passive"))
    )
    (net (code "104") (name "unconnected-(U2A-PTE23-Pad12)") (class "Default")
      (node (ref "U2") (pin "12") (pinfunction "PTE23_12") (pintype "passive"))
    )
    (net (code "105") (name "unconnected-(U2B-PTA1-Pad23)") (class "Default")
      (node (ref "U2") (pin "23") (pinfunction "PTA1_23") (pintype "passive"))
    )
    (net (code "106") (name "unconnected-(U2B-PTA2-Pad24)") (class "Default")
      (node (ref "U2") (pin "24") (pinfunction "PTA2_24") (pintype "passive"))
    )
    (net (code "107") (name "unconnected-(U2B-PTA4-Pad26)") (class "Default")
      (node (ref "U2") (pin "26") (pinfunction "PTA4_26") (pintype "passive"))
    )
    (net (code "108") (name "unconnected-(U2B-PTA5-Pad27)") (class "Default")
      (node (ref "U2") (pin "27") (pinfunction "PTA5_27") (pintype "passive"))
    )
    (net (code "109") (name "unconnected-(U2B-PTA12-Pad28)") (class "Default")
      (node (ref "U2") (pin "28") (pinfunction "PTA12_28") (pintype "passive"))
    )
    (net (code "110") (name "unconnected-(U2B-PTA13-Pad29)") (class "Default")
      (node (ref "U2") (pin "29") (pinfunction "PTA13_29") (pintype "passive"))
    )
    (net (code "111") (name "unconnected-(U2B-PTE24-Pad20)") (class "Default")
      (node (ref "U2") (pin "20") (pinfunction "PTE24_20") (pintype "passive"))
    )
    (net (code "112") (name "unconnected-(U2B-PTE25-Pad21)") (class "Default")
      (node (ref "U2") (pin "21") (pinfunction "PTE25_21") (pintype "passive"))
    )
    (net (code "113") (name "unconnected-(U2B-PTE31-Pad19)") (class "Default")
      (node (ref "U2") (pin "19") (pinfunction "PTE31_19") (pintype "passive"))
    )
    (net (code "114") (name "unconnected-(U2D-PTC5{slash}CMP_OUT-Pad50)") (class "Default")
      (node (ref "U2") (pin "50") (pinfunction "PTC5/CMP_OUT_50") (pintype "passive"))
    )
    (net (code "115") (name "unconnected-(U2D-PTC10-Pad55)") (class "Default")
      (node (ref "U2") (pin "55") (pinfunction "PTC10_55") (pintype "passive"))
    )
    (net (code "116") (name "unconnected-(U2D-PTC11-Pad56)") (class "Default")
      (node (ref "U2") (pin "56") (pinfunction "PTC11_56") (pintype "passive"))
    )
    (net (code "117") (name "unconnected-(U2D-PTD4{slash}LLWU_P14-Pad61)") (class "Default")
      (node (ref "U2") (pin "61") (pinfunction "PTD4/LLWU_P14_61") (pintype "passive"))
    )
    (net (code "118") (name "unconnected-(U2D-PTD5-Pad62)") (class "Default")
      (node (ref "U2") (pin "62") (pinfunction "PTD5_62") (pintype "passive"))
    )
    (net (code "119") (name "unconnected-(USB_1-NC-Pad4)") (class "Default")
      (node (ref "USB_1") (pin "4") (pinfunction "NC_4") (pintype "passive"))
    )
  )
)
